# EMS_esp32_wifi_lora_gsm_v2_7_1.net
KiCad netlist of a schematic drawn in EAGLE
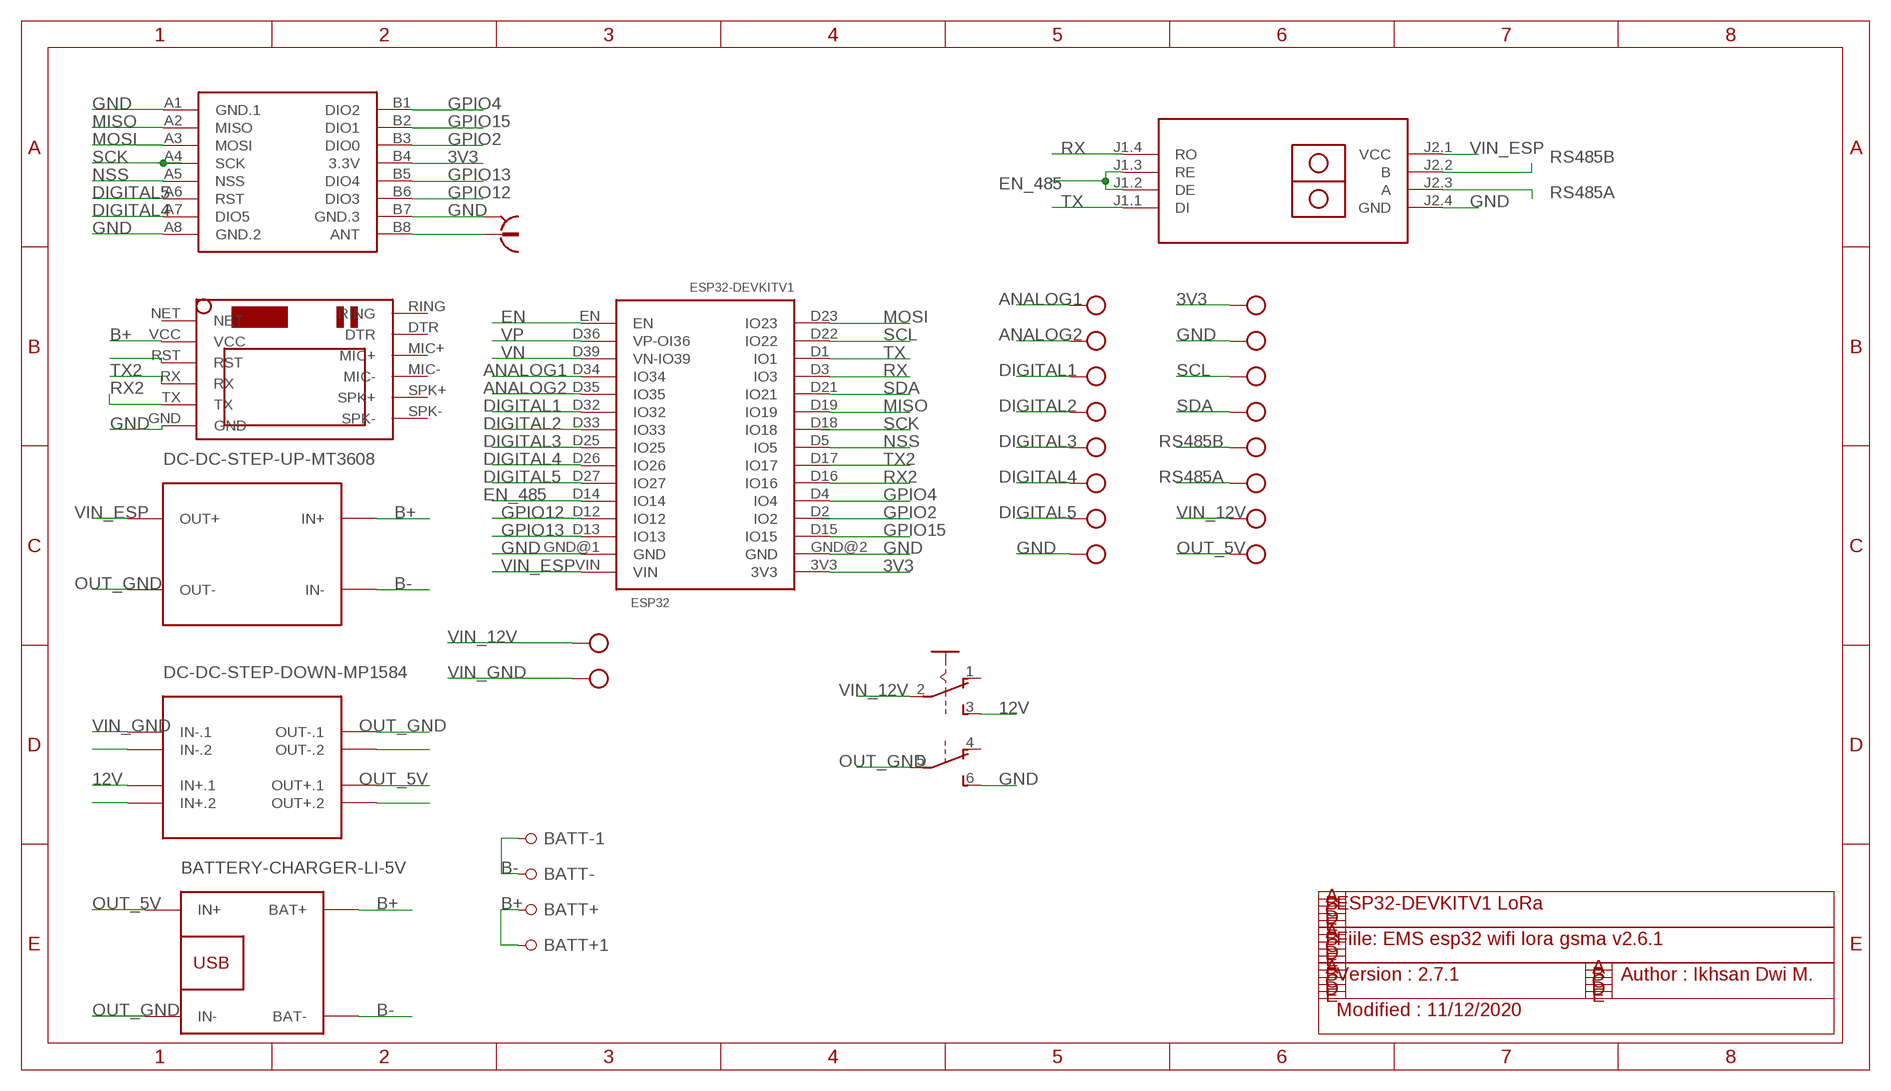
[diagram p0: schematic, sheet 1]

(export (version "E")
  (design (tool "Eeschema 10.0.6"))
  (components
    (comp (ref "BATT+")
      (value "PIN-1X1_2.00")
      (footprint "eagle-import:1X01M")
      (libsource (lib "eagle-import") (part "PIN-1X1_2.00"))
    )
    (comp (ref "BATT+1")
      (value "PIN-1X1_2.00")
      (footprint "eagle-import:1X01M")
      (libsource (lib "eagle-import") (part "PIN-1X1_2.00"))
    )
    (comp (ref "BATT-")
      (value "PIN-1X1")
      (footprint "eagle-import:1X01NONAME")
      (libsource (lib "eagle-import") (part "PIN-1X1"))
    )
    (comp (ref "BATT-1")
      (value "PIN-1X1")
      (footprint "eagle-import:1X01NONAME")
      (libsource (lib "eagle-import") (part "PIN-1X1"))
    )
    (comp (ref "ESP32")
      (value "ESP32DEVKITV1")
      (footprint "eagle-import:ESP32-DEVKITV1")
      (libsource (lib "eagle-import") (part "ESP32DEVKITV1"))
    )
    (comp (ref "S1")
      (value "A68-A31")
      (footprint "eagle-import:A68-A31")
      (libsource (lib "eagle-import") (part "A68-A31"))
    )
    (comp (ref "U$1")
      (value "RS485-TTL-CONVERTER")
      (footprint "eagle-import:RS485-TTL-CONVERTER")
      (libsource (lib "eagle-import") (part "RS485-TTL-CONVERTER"))
    )
    (comp (ref "U$2")
      (value "DC-DC-STEP-UP-MT3608")
      (footprint "eagle-import:DC-DC-STEP-UP-MT3608")
      (libsource (lib "eagle-import") (part "DC-DC-STEP-UP-MT3608"))
    )
    (comp (ref "U$3")
      (value "DC-DC-STEP-DOWN-MP1584")
      (footprint "eagle-import:DC-DC-STEP-DOWN-MP1584")
      (libsource (lib "eagle-import") (part "DC-DC-STEP-DOWN-MP1584"))
    )
    (comp (ref "U$4")
      (value "BATTERY-CHARGER-LI-5V")
      (footprint "eagle-import:BATTERY-CHARGER-LI-5V")
      (libsource (lib "eagle-import") (part "BATTERY-CHARGER-LI-5V"))
    )
    (comp (ref "U$5")
      (value "WIRELESS-LORA-RFM95W#SMD")
      (footprint "eagle-import:WIRELESS-LORA-RFM95W#SMD")
      (libsource (lib "eagle-import") (part "WIRELESS-LORA-RFM95W#SMD"))
    )
    (comp (ref "U$9")
      (value "SIM800LMODULE")
      (footprint "eagle-import:SIM800LMODULE")
      (libsource (lib "eagle-import") (part "SIM800LMODULE"))
    )
    (comp (ref "X1")
      (value "734120110")
      (footprint "eagle-import:734120110")
      (libsource (lib "eagle-import") (part "734120110"))
    )
    (comp (ref "X2")
      (value "MKDSN1,5/2-5,08")
      (footprint "eagle-import:MKDSN1,5_2-5,08")
      (libsource (lib "eagle-import") (part "MKDSN1,5/2-5,08"))
    )
    (comp (ref "X3")
      (value "MKDSN1,5/2-5,08")
      (footprint "eagle-import:MKDSN1,5_2-5,08")
      (libsource (lib "eagle-import") (part "MKDSN1,5/2-5,08"))
    )
    (comp (ref "X4")
      (value "MKDSN1,5/2-5,08")
      (footprint "eagle-import:MKDSN1,5_2-5,08")
      (libsource (lib "eagle-import") (part "MKDSN1,5/2-5,08"))
    )
    (comp (ref "X5")
      (value "MKDSN1,5/2-5,08")
      (footprint "eagle-import:MKDSN1,5_2-5,08")
      (libsource (lib "eagle-import") (part "MKDSN1,5/2-5,08"))
    )
    (comp (ref "X6")
      (value "MKDSN1,5/2-5,08")
      (footprint "eagle-import:MKDSN1,5_2-5,08")
      (libsource (lib "eagle-import") (part "MKDSN1,5/2-5,08"))
    )
    (comp (ref "X7")
      (value "MKDSN1,5/2-5,08")
      (footprint "eagle-import:MKDSN1,5_2-5,08")
      (libsource (lib "eagle-import") (part "MKDSN1,5/2-5,08"))
    )
    (comp (ref "X8")
      (value "MKDSN1,5/2-5,08")
      (footprint "eagle-import:MKDSN1,5_2-5,08")
      (libsource (lib "eagle-import") (part "MKDSN1,5/2-5,08"))
    )
    (comp (ref "X9")
      (value "MKDSN1,5/2-5,08")
      (footprint "eagle-import:MKDSN1,5_2-5,08")
      (libsource (lib "eagle-import") (part "MKDSN1,5/2-5,08"))
    )
    (comp (ref "X10")
      (value "MKDSN1,5/2-5,08")
      (footprint "eagle-import:MKDSN1,5_2-5,08")
      (libsource (lib "eagle-import") (part "MKDSN1,5/2-5,08"))
    )
  )
  (nets
    (net (code "1") (name "/3V3") (class "Default")
      (node (ref "ESP32") (pin "3V3") (pinfunction "3V3_3V3") (pintype "bidirectional"))
      (node (ref "U$5") (pin "B4") (pinfunction "3.3V_B4") (pintype "power_in"))
      (node (ref "X4") (pin "1") (pinfunction "KL_1") (pintype "passive"))
    )
    (net (code "2") (name "/12V") (class "Default")
      (node (ref "S1") (pin "3") (pinfunction "S_3") (pintype "passive"))
      (node (ref "U$3") (pin "IN+.1") (pinfunction "IN+.1_IN+.1") (pintype "bidirectional"))
    )
    (net (code "3") (name "/ANALOG1") (class "Default")
      (node (ref "ESP32") (pin "D34") (pinfunction "IO34_D34") (pintype "bidirectional"))
      (node (ref "X2") (pin "1") (pinfunction "KL_1") (pintype "passive"))
    )
    (net (code "4") (name "/ANALOG2") (class "Default")
      (node (ref "ESP32") (pin "D35") (pinfunction "IO35_D35") (pintype "bidirectional"))
      (node (ref "X2") (pin "2") (pinfunction "KL_2") (pintype "passive"))
    )
    (net (code "5") (name "/B+") (class "Default")
      (node (ref "BATT+") (pin "1") (pinfunction "1_1") (pintype "passive"))
      (node (ref "BATT+1") (pin "1") (pinfunction "1_1") (pintype "passive"))
      (node (ref "U$2") (pin "IN+") (pinfunction "IN+_IN+") (pintype "bidirectional"))
      (node (ref "U$4") (pin "BAT+") (pinfunction "BAT+_BAT+") (pintype "bidirectional"))
      (node (ref "U$9") (pin "VCC") (pinfunction "VCC_VCC") (pintype "bidirectional"))
    )
    (net (code "6") (name "/B-") (class "Default")
      (node (ref "BATT-") (pin "1") (pinfunction "1_1") (pintype "passive"))
      (node (ref "BATT-1") (pin "1") (pinfunction "1_1") (pintype "passive"))
      (node (ref "U$2") (pin "IN-") (pinfunction "IN-_IN-") (pintype "bidirectional"))
      (node (ref "U$4") (pin "BAT-") (pinfunction "BAT-_BAT-") (pintype "bidirectional"))
    )
    (net (code "7") (name "/DIGITAL1") (class "Default")
      (node (ref "ESP32") (pin "D32") (pinfunction "IO32_D32") (pintype "bidirectional"))
      (node (ref "X3") (pin "1") (pinfunction "KL_1") (pintype "passive"))
    )
    (net (code "8") (name "/DIGITAL2") (class "Default")
      (node (ref "ESP32") (pin "D33") (pinfunction "IO33_D33") (pintype "bidirectional"))
      (node (ref "X3") (pin "2") (pinfunction "KL_2") (pintype "passive"))
    )
    (net (code "9") (name "/DIGITAL3") (class "Default")
      (node (ref "ESP32") (pin "D25") (pinfunction "IO25_D25") (pintype "bidirectional"))
      (node (ref "X5") (pin "1") (pinfunction "KL_1") (pintype "passive"))
    )
    (net (code "10") (name "/DIGITAL4") (class "Default")
      (node (ref "ESP32") (pin "D26") (pinfunction "IO26_D26") (pintype "bidirectional"))
      (node (ref "U$5") (pin "A7") (pinfunction "DIO5_A7") (pintype "bidirectional"))
      (node (ref "X5") (pin "2") (pinfunction "KL_2") (pintype "passive"))
    )
    (net (code "11") (name "/DIGITAL5") (class "Default")
      (node (ref "ESP32") (pin "D27") (pinfunction "IO27_D27") (pintype "bidirectional"))
      (node (ref "U$5") (pin "A6") (pinfunction "RST_A6") (pintype "bidirectional"))
      (node (ref "X6") (pin "1") (pinfunction "KL_1") (pintype "passive"))
    )
    (net (code "12") (name "/EN") (class "Default")
      (node (ref "ESP32") (pin "EN") (pinfunction "EN_EN") (pintype "bidirectional"))
    )
    (net (code "13") (name "/EN_485") (class "Default")
      (node (ref "ESP32") (pin "D14") (pinfunction "IO14_D14") (pintype "bidirectional"))
      (node (ref "U$1") (pin "J1.2") (pinfunction "DE_J1.2") (pintype "passive"))
      (node (ref "U$1") (pin "J1.3") (pinfunction "RE_J1.3") (pintype "passive"))
    )
    (net (code "14") (name "/GND") (class "Default")
      (node (ref "ESP32") (pin "GND@1") (pinfunction "GND_GND@1") (pintype "bidirectional"))
      (node (ref "ESP32") (pin "GND@2") (pinfunction "GND_GND@2") (pintype "bidirectional"))
      (node (ref "S1") (pin "6") (pinfunction "S_6") (pintype "passive"))
      (node (ref "U$1") (pin "J2.4") (pinfunction "GND_J2.4") (pintype "power_in"))
      (node (ref "U$5") (pin "A1") (pinfunction "GND.1_A1") (pintype "power_in"))
      (node (ref "U$5") (pin "A8") (pinfunction "GND.2_A8") (pintype "power_in"))
      (node (ref "U$5") (pin "B7") (pinfunction "GND.3_B7") (pintype "power_in"))
      (node (ref "U$9") (pin "GND") (pinfunction "GND_GND") (pintype "bidirectional"))
      (node (ref "X1") (pin "S@1") (pinfunction "2_S@1") (pintype "passive"))
      (node (ref "X1") (pin "S@2") (pinfunction "2_S@2") (pintype "passive"))
      (node (ref "X1") (pin "S@3") (pinfunction "2_S@3") (pintype "passive"))
      (node (ref "X4") (pin "2") (pinfunction "KL_2") (pintype "passive"))
      (node (ref "X6") (pin "2") (pinfunction "KL_2") (pintype "passive"))
    )
    (net (code "15") (name "/GPIO2") (class "Default")
      (node (ref "ESP32") (pin "D2") (pinfunction "IO2_D2") (pintype "bidirectional"))
      (node (ref "U$5") (pin "B3") (pinfunction "DIO0_B3") (pintype "bidirectional"))
    )
    (net (code "16") (name "/GPIO4") (class "Default")
      (node (ref "ESP32") (pin "D4") (pinfunction "IO4_D4") (pintype "bidirectional"))
      (node (ref "U$5") (pin "B1") (pinfunction "DIO2_B1") (pintype "bidirectional"))
    )
    (net (code "17") (name "/GPIO12") (class "Default")
      (node (ref "ESP32") (pin "D12") (pinfunction "IO12_D12") (pintype "bidirectional"))
      (node (ref "U$5") (pin "B6") (pinfunction "DIO3_B6") (pintype "bidirectional"))
    )
    (net (code "18") (name "/GPIO13") (class "Default")
      (node (ref "ESP32") (pin "D13") (pinfunction "IO13_D13") (pintype "bidirectional"))
      (node (ref "U$5") (pin "B5") (pinfunction "DIO4_B5") (pintype "bidirectional"))
    )
    (net (code "19") (name "/GPIO15") (class "Default")
      (node (ref "ESP32") (pin "D15") (pinfunction "IO15_D15") (pintype "bidirectional"))
      (node (ref "U$5") (pin "B2") (pinfunction "DIO1_B2") (pintype "bidirectional"))
    )
    (net (code "20") (name "/MISO") (class "Default")
      (node (ref "ESP32") (pin "D19") (pinfunction "IO19_D19") (pintype "bidirectional"))
      (node (ref "U$5") (pin "A2") (pinfunction "MISO_A2") (pintype "bidirectional"))
    )
    (net (code "21") (name "/MOSI") (class "Default")
      (node (ref "ESP32") (pin "D23") (pinfunction "IO23_D23") (pintype "bidirectional"))
      (node (ref "U$5") (pin "A3") (pinfunction "MOSI_A3") (pintype "bidirectional"))
    )
    (net (code "22") (name "/NSS") (class "Default")
      (node (ref "ESP32") (pin "D5") (pinfunction "IO5_D5") (pintype "bidirectional"))
      (node (ref "U$5") (pin "A5") (pinfunction "NSS_A5") (pintype "bidirectional"))
    )
    (net (code "23") (name "/OUT_5V") (class "Default")
      (node (ref "U$3") (pin "OUT+.1") (pinfunction "OUT+.1_OUT+.1") (pintype "bidirectional"))
      (node (ref "U$4") (pin "IN+") (pinfunction "IN+_IN+") (pintype "bidirectional"))
      (node (ref "X9") (pin "2") (pinfunction "KL_2") (pintype "passive"))
    )
    (net (code "24") (name "/OUT_GND") (class "Default")
      (node (ref "S1") (pin "5") (pinfunction "P_5") (pintype "passive"))
      (node (ref "U$2") (pin "OUT-") (pinfunction "OUT-_OUT-") (pintype "bidirectional"))
      (node (ref "U$3") (pin "OUT-.1") (pinfunction "OUT-.1_OUT-.1") (pintype "bidirectional"))
      (node (ref "U$4") (pin "IN-") (pinfunction "IN-_IN-") (pintype "bidirectional"))
    )
    (net (code "25") (name "/RS485A") (class "Default")
      (node (ref "U$1") (pin "J2.3") (pinfunction "A_J2.3") (pintype "passive"))
      (node (ref "X8") (pin "2") (pinfunction "KL_2") (pintype "passive"))
    )
    (net (code "26") (name "/RS485B") (class "Default")
      (node (ref "U$1") (pin "J2.2") (pinfunction "B_J2.2") (pintype "passive"))
      (node (ref "X8") (pin "1") (pinfunction "KL_1") (pintype "passive"))
    )
    (net (code "27") (name "/RX") (class "Default")
      (node (ref "ESP32") (pin "D3") (pinfunction "IO3_D3") (pintype "bidirectional"))
      (node (ref "U$1") (pin "J1.4") (pinfunction "RO_J1.4") (pintype "passive"))
    )
    (net (code "28") (name "/RX2") (class "Default")
      (node (ref "ESP32") (pin "D16") (pinfunction "IO16_D16") (pintype "bidirectional"))
      (node (ref "U$9") (pin "TX") (pinfunction "TX_TX") (pintype "bidirectional"))
    )
    (net (code "29") (name "/SCK") (class "Default")
      (node (ref "ESP32") (pin "D18") (pinfunction "IO18_D18") (pintype "bidirectional"))
      (node (ref "U$5") (pin "A4") (pinfunction "SCK_A4") (pintype "bidirectional"))
    )
    (net (code "30") (name "/SCL") (class "Default")
      (node (ref "ESP32") (pin "D22") (pinfunction "IO22_D22") (pintype "bidirectional"))
      (node (ref "X7") (pin "1") (pinfunction "KL_1") (pintype "passive"))
    )
    (net (code "31") (name "/SDA") (class "Default")
      (node (ref "ESP32") (pin "D21") (pinfunction "IO21_D21") (pintype "bidirectional"))
      (node (ref "X7") (pin "2") (pinfunction "KL_2") (pintype "passive"))
    )
    (net (code "32") (name "/TX") (class "Default")
      (node (ref "ESP32") (pin "D1") (pinfunction "IO1_D1") (pintype "bidirectional"))
      (node (ref "U$1") (pin "J1.1") (pinfunction "DI_J1.1") (pintype "passive"))
    )
    (net (code "33") (name "/TX2") (class "Default")
      (node (ref "ESP32") (pin "D17") (pinfunction "IO17_D17") (pintype "bidirectional"))
      (node (ref "U$9") (pin "RX") (pinfunction "RX_RX") (pintype "bidirectional"))
    )
    (net (code "34") (name "/VIN_12V") (class "Default")
      (node (ref "S1") (pin "2") (pinfunction "P_2") (pintype "passive"))
      (node (ref "X10") (pin "1") (pinfunction "KL_1") (pintype "passive"))
      (node (ref "X9") (pin "1") (pinfunction "KL_1") (pintype "passive"))
    )
    (net (code "35") (name "/VIN_ESP") (class "Default")
      (node (ref "ESP32") (pin "VIN") (pinfunction "VIN_VIN") (pintype "bidirectional"))
      (node (ref "U$1") (pin "J2.1") (pinfunction "VCC_J2.1") (pintype "power_in"))
      (node (ref "U$2") (pin "OUT+") (pinfunction "OUT+_OUT+") (pintype "bidirectional"))
    )
    (net (code "36") (name "/VIN_GND") (class "Default")
      (node (ref "U$3") (pin "IN-.1") (pinfunction "IN-.1_IN-.1") (pintype "bidirectional"))
      (node (ref "X10") (pin "2") (pinfunction "KL_2") (pintype "passive"))
    )
    (net (code "37") (name "/VN") (class "Default")
      (node (ref "ESP32") (pin "D39") (pinfunction "VN-IO39_D39") (pintype "bidirectional"))
    )
    (net (code "38") (name "/VP") (class "Default")
      (node (ref "ESP32") (pin "D36") (pinfunction "VP-OI36_D36") (pintype "bidirectional"))
    )
    (net (code "39") (name "Net-(U$5-ANT)") (class "Default")
      (node (ref "U$5") (pin "B8") (pinfunction "ANT_B8") (pintype "passive"))
      (node (ref "X1") (pin "1") (pinfunction "1_1") (pintype "passive"))
    )
    (net (code "40") (name "unconnected-(S1A-O-Pad1)") (class "Default")
      (node (ref "S1") (pin "1") (pinfunction "O_1") (pintype "passive"))
    )
    (net (code "41") (name "unconnected-(S1B-O-Pad4)") (class "Default")
      (node (ref "S1") (pin "4") (pinfunction "O_4") (pintype "passive"))
    )
    (net (code "42") (name "unconnected-(U$3-PadIN+.2)") (class "Default")
      (node (ref "U$3") (pin "IN+.2") (pinfunction "IN+.2_IN+.2") (pintype "bidirectional"))
    )
    (net (code "43") (name "unconnected-(U$3-PadIN-.2)") (class "Default")
      (node (ref "U$3") (pin "IN-.2") (pinfunction "IN-.2_IN-.2") (pintype "bidirectional"))
    )
    (net (code "44") (name "unconnected-(U$3-PadOUT+.2)") (class "Default")
      (node (ref "U$3") (pin "OUT+.2") (pinfunction "OUT+.2_OUT+.2") (pintype "bidirectional"))
    )
    (net (code "45") (name "unconnected-(U$3-PadOUT-.2)") (class "Default")
      (node (ref "U$3") (pin "OUT-.2") (pinfunction "OUT-.2_OUT-.2") (pintype "bidirectional"))
    )
    (net (code "46") (name "unconnected-(U$9-PadDTR)") (class "Default")
      (node (ref "U$9") (pin "DTR") (pinfunction "DTR_DTR") (pintype "bidirectional"))
    )
    (net (code "47") (name "unconnected-(U$9-PadMIC+)") (class "Default")
      (node (ref "U$9") (pin "MIC+") (pinfunction "MIC+_MIC+") (pintype "bidirectional"))
    )
    (net (code "48") (name "unconnected-(U$9-PadMIC-)") (class "Default")
      (node (ref "U$9") (pin "MIC-") (pinfunction "MIC-_MIC-") (pintype "bidirectional"))
    )
    (net (code "49") (name "unconnected-(U$9-PadNET)") (class "Default")
      (node (ref "U$9") (pin "NET") (pinfunction "NET_NET") (pintype "bidirectional"))
    )
    (net (code "50") (name "unconnected-(U$9-PadRING)") (class "Default")
      (node (ref "U$9") (pin "RING") (pinfunction "RING_RING") (pintype "bidirectional"))
    )
    (net (code "51") (name "unconnected-(U$9-PadRST)") (class "Default")
      (node (ref "U$9") (pin "RST") (pinfunction "RST_RST") (pintype "bidirectional"))
    )
    (net (code "52") (name "unconnected-(U$9-PadSPK+)") (class "Default")
      (node (ref "U$9") (pin "SPK+") (pinfunction "SPK+_SPK+") (pintype "bidirectional"))
    )
    (net (code "53") (name "unconnected-(U$9-PadSPK-)") (class "Default")
      (node (ref "U$9") (pin "SPK-") (pinfunction "SPK-_SPK-") (pintype "bidirectional"))
    )
  )
)
